# Carduino_v20.net
KiCad netlist of a schematic drawn in EAGLE
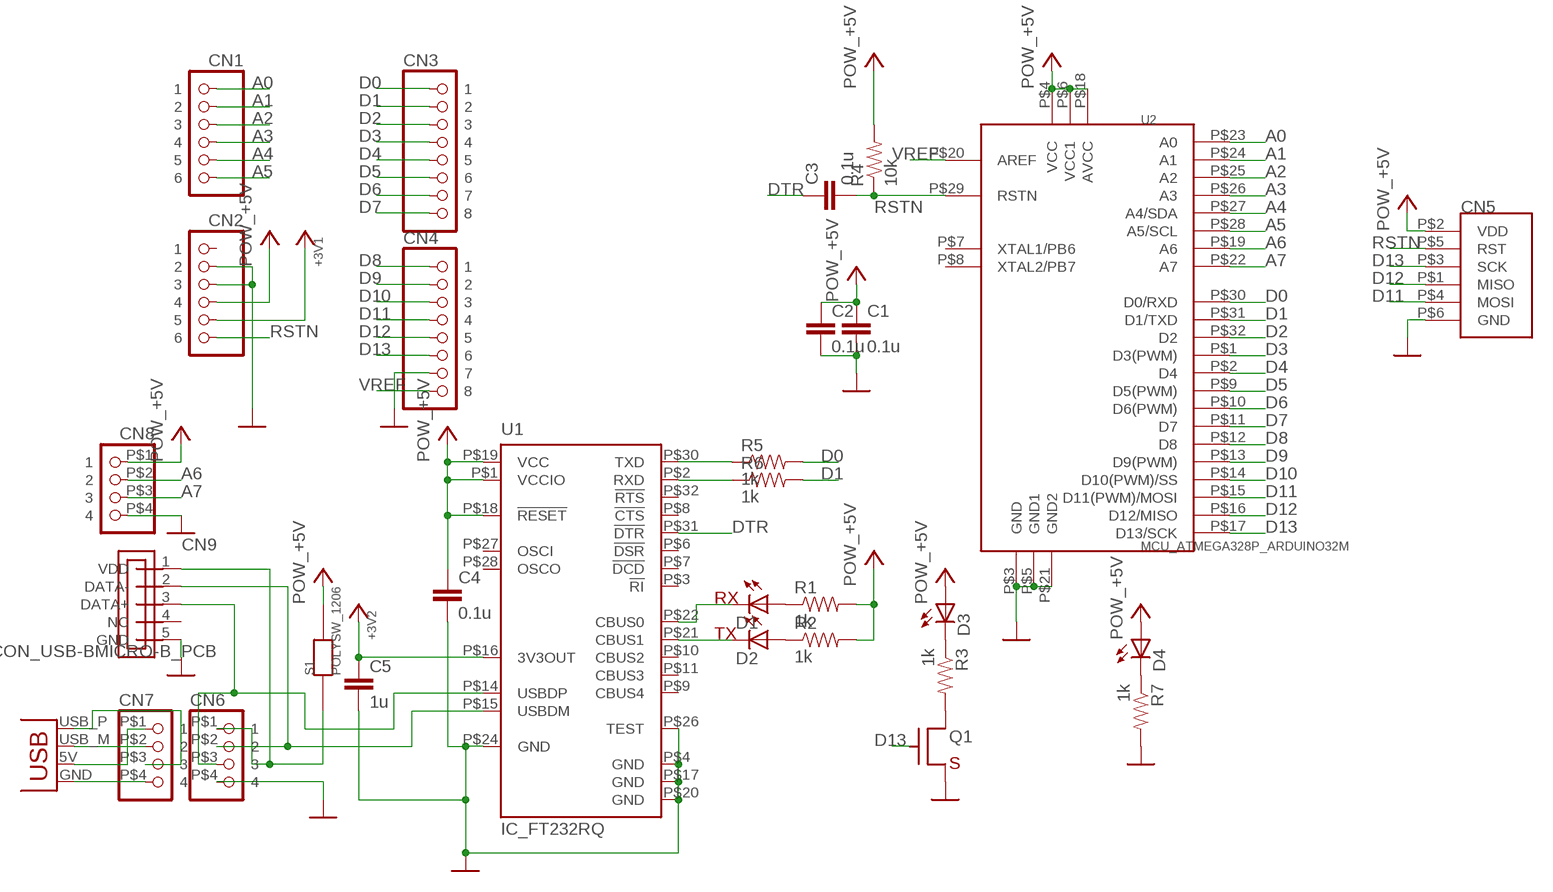
[diagram p0: schematic, sheet 1]

(export (version "E")
  (design (tool "Eeschema 10.0.6"))
  (components
    (comp (ref "C1")
      (value "0.1u")
      (footprint "eagle-import:0603")
      (libsource (lib "eagle-import") (part "CAP0603"))
    )
    (comp (ref "C2")
      (value "0.1u")
      (footprint "eagle-import:0603")
      (libsource (lib "eagle-import") (part "CAP0603"))
    )
    (comp (ref "C3")
      (value "0.1u")
      (footprint "eagle-import:0603")
      (libsource (lib "eagle-import") (part "CAP0603"))
    )
    (comp (ref "C4")
      (value "0.1u")
      (footprint "eagle-import:0603")
      (libsource (lib "eagle-import") (part "CAP0603"))
    )
    (comp (ref "C5")
      (value "1u")
      (footprint "eagle-import:0603")
      (libsource (lib "eagle-import") (part "CAP0603"))
    )
    (comp (ref "CN1")
      (value "CON_PINHD-1X6SMD")
      (footprint "eagle-import:1X06SMD")
      (libsource (lib "eagle-import") (part "CON_PINHD-1X6SMD"))
    )
    (comp (ref "CN2")
      (value "CON_PINHD-1X6SMD")
      (footprint "eagle-import:1X06SMD")
      (libsource (lib "eagle-import") (part "CON_PINHD-1X6SMD"))
    )
    (comp (ref "CN3")
      (value "CON_PINHD-1X8SMD")
      (footprint "eagle-import:1X08SMD")
      (libsource (lib "eagle-import") (part "CON_PINHD-1X8SMD"))
    )
    (comp (ref "CN4")
      (value "CON_PINHD-1X8SMD")
      (footprint "eagle-import:1X08SMD")
      (libsource (lib "eagle-import") (part "CON_PINHD-1X8SMD"))
    )
    (comp (ref "CN5")
      (value "CON_AVRISPSMD")
      (footprint "eagle-import:2X3SMD")
      (libsource (lib "eagle-import") (part "CON_AVRISPSMD"))
    )
    (comp (ref "CN6")
      (value "CON_PINHD-1X4SMD")
      (footprint "eagle-import:1X04SMD")
      (libsource (lib "eagle-import") (part "CON_PINHD-1X4SMD"))
    )
    (comp (ref "CN7")
      (value "CON_PINHD-1X4SMD")
      (footprint "eagle-import:1X04SMD")
      (libsource (lib "eagle-import") (part "CON_PINHD-1X4SMD"))
    )
    (comp (ref "CN8")
      (value "CON_PINHD-1X4SMD")
      (footprint "eagle-import:1X04SMD")
      (libsource (lib "eagle-import") (part "CON_PINHD-1X4SMD"))
    )
    (comp (ref "CN9")
      (value "CON_USB-BMICRO-B_PCB")
      (footprint "eagle-import:USB-MICRO-PCB")
      (libsource (lib "eagle-import") (part "CON_USB-BMICRO-B_PCB"))
    )
    (comp (ref "D1")
      (value "LED0603")
      (footprint "eagle-import:SPARKFUN_LED-0603")
      (libsource (lib "eagle-import") (part "LED0603"))
    )
    (comp (ref "D2")
      (value "LED0603")
      (footprint "eagle-import:SPARKFUN_LED-0603")
      (libsource (lib "eagle-import") (part "LED0603"))
    )
    (comp (ref "D3")
      (value "LED0603")
      (footprint "eagle-import:SPARKFUN_LED-0603")
      (libsource (lib "eagle-import") (part "LED0603"))
    )
    (comp (ref "D4")
      (value "LED0603")
      (footprint "eagle-import:SPARKFUN_LED-0603")
      (libsource (lib "eagle-import") (part "LED0603"))
    )
    (comp (ref "JP2")
      (value "CON_USBPCB")
      (footprint "eagle-import:USB-A-PCB")
      (libsource (lib "eagle-import") (part "CON_USBPCB"))
    )
    (comp (ref "Q1")
      (value "TR_NMOS_IRLML6344")
      (footprint "eagle-import:SOT-23-3-2916")
      (libsource (lib "eagle-import") (part "TR_NMOS_IRLML6344"))
    )
    (comp (ref "R1")
      (value "1k")
      (footprint "eagle-import:0603")
      (libsource (lib "eagle-import") (part "RES0603"))
    )
    (comp (ref "R2")
      (value "1k")
      (footprint "eagle-import:0603")
      (libsource (lib "eagle-import") (part "RES0603"))
    )
    (comp (ref "R3")
      (value "1k")
      (footprint "eagle-import:0603")
      (libsource (lib "eagle-import") (part "RES0603"))
    )
    (comp (ref "R4")
      (value "10k")
      (footprint "eagle-import:0603")
      (libsource (lib "eagle-import") (part "RES0603"))
    )
    (comp (ref "R5")
      (value "1k")
      (footprint "eagle-import:0603")
      (libsource (lib "eagle-import") (part "RES0603"))
    )
    (comp (ref "R6")
      (value "1k")
      (footprint "eagle-import:0603")
      (libsource (lib "eagle-import") (part "RES0603"))
    )
    (comp (ref "R7")
      (value "1k")
      (footprint "eagle-import:0603")
      (libsource (lib "eagle-import") (part "RES0603"))
    )
    (comp (ref "S1")
      (value "POLYSW_1206")
      (footprint "eagle-import:1206")
      (libsource (lib "eagle-import") (part "POLYSW_1206"))
    )
    (comp (ref "U1")
      (value "IC_FT232RQ")
      (footprint "eagle-import:QFN32")
      (libsource (lib "eagle-import") (part "IC_FT232RQ"))
    )
    (comp (ref "U2")
      (value "MCU_ATMEGA328P_ARDUINO32M")
      (footprint "eagle-import:QFN32")
      (libsource (lib "eagle-import") (part "MCU_ATMEGA328P_ARDUINO32M"))
    )
  )
  (nets
    (net (code "1") (name "/A0") (class "Default")
      (node (ref "CN1") (pin "P$1") (pinfunction "1_P$1") (pintype "passive"))
      (node (ref "U2") (pin "P$23") (pinfunction "A0_P$23") (pintype "bidirectional"))
    )
    (net (code "2") (name "/A1") (class "Default")
      (node (ref "CN1") (pin "P$2") (pinfunction "2_P$2") (pintype "passive"))
      (node (ref "U2") (pin "P$24") (pinfunction "A1_P$24") (pintype "bidirectional"))
    )
    (net (code "3") (name "/A2") (class "Default")
      (node (ref "CN1") (pin "P$3") (pinfunction "3_P$3") (pintype "passive"))
      (node (ref "U2") (pin "P$25") (pinfunction "A2_P$25") (pintype "bidirectional"))
    )
    (net (code "4") (name "/A3") (class "Default")
      (node (ref "CN1") (pin "P$4") (pinfunction "4_P$4") (pintype "passive"))
      (node (ref "U2") (pin "P$26") (pinfunction "A3_P$26") (pintype "bidirectional"))
    )
    (net (code "5") (name "/A4") (class "Default")
      (node (ref "CN1") (pin "P$5") (pinfunction "5_P$5") (pintype "passive"))
      (node (ref "U2") (pin "P$27") (pinfunction "A4/SDA_P$27") (pintype "bidirectional"))
    )
    (net (code "6") (name "/A5") (class "Default")
      (node (ref "CN1") (pin "P$6") (pinfunction "6_P$6") (pintype "passive"))
      (node (ref "U2") (pin "P$28") (pinfunction "A5/SCL_P$28") (pintype "bidirectional"))
    )
    (net (code "7") (name "/A6") (class "Default")
      (node (ref "CN8") (pin "P$2") (pinfunction "2_P$2") (pintype "passive"))
      (node (ref "U2") (pin "P$19") (pinfunction "A6_P$19") (pintype "bidirectional"))
    )
    (net (code "8") (name "/A7") (class "Default")
      (node (ref "CN8") (pin "P$3") (pinfunction "3_P$3") (pintype "passive"))
      (node (ref "U2") (pin "P$22") (pinfunction "A7_P$22") (pintype "bidirectional"))
    )
    (net (code "9") (name "/D0") (class "Default")
      (node (ref "CN3") (pin "P$1") (pinfunction "1_P$1") (pintype "passive"))
      (node (ref "R5") (pin "2") (pinfunction "2_2") (pintype "passive"))
      (node (ref "U2") (pin "P$30") (pinfunction "D0/RXD_P$30") (pintype "bidirectional"))
    )
    (net (code "10") (name "/D1") (class "Default")
      (node (ref "CN3") (pin "P$2") (pinfunction "2_P$2") (pintype "passive"))
      (node (ref "R6") (pin "2") (pinfunction "2_2") (pintype "passive"))
      (node (ref "U2") (pin "P$31") (pinfunction "D1/TXD_P$31") (pintype "bidirectional"))
    )
    (net (code "11") (name "/D2") (class "Default")
      (node (ref "CN3") (pin "P$3") (pinfunction "3_P$3") (pintype "passive"))
      (node (ref "U2") (pin "P$32") (pinfunction "D2_P$32") (pintype "bidirectional"))
    )
    (net (code "12") (name "/D3") (class "Default")
      (node (ref "CN3") (pin "P$4") (pinfunction "4_P$4") (pintype "passive"))
      (node (ref "U2") (pin "P$1") (pinfunction "D3(PWM)_P$1") (pintype "bidirectional"))
    )
    (net (code "13") (name "/D4") (class "Default")
      (node (ref "CN3") (pin "P$5") (pinfunction "5_P$5") (pintype "passive"))
      (node (ref "U2") (pin "P$2") (pinfunction "D4_P$2") (pintype "bidirectional"))
    )
    (net (code "14") (name "/D5") (class "Default")
      (node (ref "CN3") (pin "P$6") (pinfunction "6_P$6") (pintype "passive"))
      (node (ref "U2") (pin "P$9") (pinfunction "D5(PWM)_P$9") (pintype "bidirectional"))
    )
    (net (code "15") (name "/D6") (class "Default")
      (node (ref "CN3") (pin "P$7") (pinfunction "7_P$7") (pintype "passive"))
      (node (ref "U2") (pin "P$10") (pinfunction "D6(PWM)_P$10") (pintype "bidirectional"))
    )
    (net (code "16") (name "/D7") (class "Default")
      (node (ref "CN3") (pin "P$8") (pinfunction "8_P$8") (pintype "passive"))
      (node (ref "U2") (pin "P$11") (pinfunction "D7_P$11") (pintype "bidirectional"))
    )
    (net (code "17") (name "/D8") (class "Default")
      (node (ref "CN4") (pin "P$1") (pinfunction "1_P$1") (pintype "passive"))
      (node (ref "U2") (pin "P$12") (pinfunction "D8_P$12") (pintype "bidirectional"))
    )
    (net (code "18") (name "/D9") (class "Default")
      (node (ref "CN4") (pin "P$2") (pinfunction "2_P$2") (pintype "passive"))
      (node (ref "U2") (pin "P$13") (pinfunction "D9(PWM)_P$13") (pintype "bidirectional"))
    )
    (net (code "19") (name "/D10") (class "Default")
      (node (ref "CN4") (pin "P$3") (pinfunction "3_P$3") (pintype "passive"))
      (node (ref "U2") (pin "P$14") (pinfunction "D10(PWM)/SS_P$14") (pintype "bidirectional"))
    )
    (net (code "20") (name "/D11") (class "Default")
      (node (ref "CN4") (pin "P$4") (pinfunction "4_P$4") (pintype "passive"))
      (node (ref "CN5") (pin "P$4") (pinfunction "MOSI_P$4") (pintype "bidirectional"))
      (node (ref "U2") (pin "P$15") (pinfunction "D11(PWM)/MOSI_P$15") (pintype "bidirectional"))
    )
    (net (code "21") (name "/D12") (class "Default")
      (node (ref "CN4") (pin "P$5") (pinfunction "5_P$5") (pintype "passive"))
      (node (ref "CN5") (pin "P$1") (pinfunction "MISO_P$1") (pintype "bidirectional"))
      (node (ref "U2") (pin "P$16") (pinfunction "D12/MISO_P$16") (pintype "bidirectional"))
    )
    (net (code "22") (name "/D13") (class "Default")
      (node (ref "CN4") (pin "P$6") (pinfunction "6_P$6") (pintype "passive"))
      (node (ref "CN5") (pin "P$3") (pinfunction "SCK_P$3") (pintype "bidirectional"))
      (node (ref "Q1") (pin "1") (pinfunction "G_1") (pintype "bidirectional"))
      (node (ref "U2") (pin "P$17") (pinfunction "D13/SCK_P$17") (pintype "bidirectional"))
    )
    (net (code "23") (name "/DTR") (class "Default")
      (node (ref "C3") (pin "1") (pinfunction "1_1") (pintype "passive"))
      (node (ref "U1") (pin "P$31") (pinfunction "~{DTR}_P$31") (pintype "output"))
    )
    (net (code "24") (name "/RSTN") (class "Default")
      (node (ref "C3") (pin "2") (pinfunction "2_2") (pintype "passive"))
      (node (ref "CN2") (pin "P$6") (pinfunction "6_P$6") (pintype "passive"))
      (node (ref "CN5") (pin "P$5") (pinfunction "RST_P$5") (pintype "bidirectional"))
      (node (ref "R4") (pin "1") (pinfunction "1_1") (pintype "passive"))
      (node (ref "U2") (pin "P$29") (pinfunction "RSTN_P$29") (pintype "bidirectional"))
    )
    (net (code "25") (name "/VREF") (class "Default")
      (node (ref "CN4") (pin "P$8") (pinfunction "8_P$8") (pintype "passive"))
      (node (ref "U2") (pin "P$20") (pinfunction "AREF_P$20") (pintype "bidirectional"))
    )
    (net (code "26") (name "Net-(CN6-1)") (class "Default")
      (node (ref "CN6") (pin "P$1") (pinfunction "1_P$1") (pintype "passive"))
      (node (ref "CN9") (pin "1") (pinfunction "VDD_1") (pintype "power_in"))
      (node (ref "S1") (pin "P$1") (pinfunction "P$1_P$1") (pintype "bidirectional"))
    )
    (net (code "27") (name "Net-(CN6-2)") (class "Default")
      (node (ref "CN6") (pin "P$2") (pinfunction "2_P$2") (pintype "passive"))
      (node (ref "CN9") (pin "2") (pinfunction "DATA-_2") (pintype "bidirectional"))
      (node (ref "U1") (pin "P$15") (pinfunction "USBDM_P$15") (pintype "bidirectional"))
    )
    (net (code "28") (name "Net-(CN6-3)") (class "Default")
      (node (ref "CN6") (pin "P$3") (pinfunction "3_P$3") (pintype "passive"))
      (node (ref "CN9") (pin "3") (pinfunction "DATA+_3") (pintype "bidirectional"))
      (node (ref "U1") (pin "P$14") (pinfunction "USBDP_P$14") (pintype "bidirectional"))
    )
    (net (code "29") (name "Net-(CN7-1)") (class "Default")
      (node (ref "CN7") (pin "P$1") (pinfunction "1_P$1") (pintype "passive"))
      (node (ref "JP2") (pin "5V") (pinfunction "VBUS_5V") (pintype "bidirectional"))
    )
    (net (code "30") (name "Net-(CN7-2)") (class "Default")
      (node (ref "CN7") (pin "P$2") (pinfunction "2_P$2") (pintype "passive"))
      (node (ref "JP2") (pin "USB_M") (pinfunction "D-_USB_M") (pintype "bidirectional"))
    )
    (net (code "31") (name "Net-(CN7-3)") (class "Default")
      (node (ref "CN7") (pin "P$3") (pinfunction "3_P$3") (pintype "passive"))
      (node (ref "JP2") (pin "USB_P") (pinfunction "D+_USB_P") (pintype "bidirectional"))
    )
    (net (code "32") (name "Net-(CN7-4)") (class "Default")
      (node (ref "CN7") (pin "P$4") (pinfunction "4_P$4") (pintype "passive"))
      (node (ref "JP2") (pin "GND") (pinfunction "GND_GND") (pintype "bidirectional"))
    )
    (net (code "33") (name "Net-(D1-PadA)") (class "Default")
      (node (ref "D1") (pin "A") (pinfunction "A_A") (pintype "passive"))
      (node (ref "R1") (pin "1") (pinfunction "1_1") (pintype "passive"))
    )
    (net (code "34") (name "Net-(D2-PadA)") (class "Default")
      (node (ref "D2") (pin "A") (pinfunction "A_A") (pintype "passive"))
      (node (ref "R2") (pin "1") (pinfunction "1_1") (pintype "passive"))
    )
    (net (code "35") (name "Net-(D3-PadC)") (class "Default")
      (node (ref "D3") (pin "C") (pinfunction "C_C") (pintype "passive"))
      (node (ref "R3") (pin "1") (pinfunction "1_1") (pintype "passive"))
    )
    (net (code "36") (name "Net-(D4-PadC)") (class "Default")
      (node (ref "D4") (pin "C") (pinfunction "C_C") (pintype "passive"))
      (node (ref "R7") (pin "1") (pinfunction "1_1") (pintype "passive"))
    )
    (net (code "37") (name "Net-(Q1-D)") (class "Default")
      (node (ref "Q1") (pin "3") (pinfunction "D_3") (pintype "bidirectional"))
      (node (ref "R3") (pin "2") (pinfunction "2_2") (pintype "passive"))
    )
    (net (code "38") (name "Net-(U1-CBUS0)") (class "Default")
      (node (ref "D1") (pin "C") (pinfunction "C_C") (pintype "passive"))
      (node (ref "U1") (pin "P$22") (pinfunction "CBUS0_P$22") (pintype "bidirectional"))
    )
    (net (code "39") (name "Net-(U1-CBUS1)") (class "Default")
      (node (ref "D2") (pin "C") (pinfunction "C_C") (pintype "passive"))
      (node (ref "U1") (pin "P$21") (pinfunction "CBUS1_P$21") (pintype "bidirectional"))
    )
    (net (code "40") (name "Net-(U1-RXD)") (class "Default")
      (node (ref "R6") (pin "1") (pinfunction "1_1") (pintype "passive"))
      (node (ref "U1") (pin "P$2") (pinfunction "RXD_P$2") (pintype "input"))
    )
    (net (code "41") (name "Net-(U1-TXD)") (class "Default")
      (node (ref "R5") (pin "1") (pinfunction "1_1") (pintype "passive"))
      (node (ref "U1") (pin "P$30") (pinfunction "TXD_P$30") (pintype "output"))
    )
    (net (code "42") (name "POW_+3V3") (class "Default")
      (node (ref "C5") (pin "1") (pinfunction "1_1") (pintype "passive"))
      (node (ref "CN2") (pin "P$5") (pinfunction "5_P$5") (pintype "passive"))
      (node (ref "U1") (pin "P$16") (pinfunction "3V3OUT_P$16") (pintype "output"))
    )
    (net (code "43") (name "POW_+5V") (class "Default")
      (node (ref "C1") (pin "1") (pinfunction "1_1") (pintype "passive"))
      (node (ref "C2") (pin "1") (pinfunction "1_1") (pintype "passive"))
      (node (ref "C4") (pin "1") (pinfunction "1_1") (pintype "passive"))
      (node (ref "CN2") (pin "P$4") (pinfunction "4_P$4") (pintype "passive"))
      (node (ref "CN5") (pin "P$2") (pinfunction "VDD_P$2") (pintype "bidirectional"))
      (node (ref "CN8") (pin "P$1") (pinfunction "1_P$1") (pintype "passive"))
      (node (ref "D3") (pin "A") (pinfunction "A_A") (pintype "passive"))
      (node (ref "D4") (pin "A") (pinfunction "A_A") (pintype "passive"))
      (node (ref "R1") (pin "2") (pinfunction "2_2") (pintype "passive"))
      (node (ref "R2") (pin "2") (pinfunction "2_2") (pintype "passive"))
      (node (ref "R4") (pin "2") (pinfunction "2_2") (pintype "passive"))
      (node (ref "S1") (pin "P$2") (pinfunction "P$2_P$2") (pintype "bidirectional"))
      (node (ref "U1") (pin "P$1") (pinfunction "VCCIO_P$1") (pintype "power_in"))
      (node (ref "U1") (pin "P$18") (pinfunction "~{RESET}_P$18") (pintype "input"))
      (node (ref "U1") (pin "P$19") (pinfunction "VCC_P$19") (pintype "power_in"))
      (node (ref "U2") (pin "P$18") (pinfunction "AVCC_P$18") (pintype "power_in"))
      (node (ref "U2") (pin "P$4") (pinfunction "VCC_P$4") (pintype "power_in"))
      (node (ref "U2") (pin "P$6") (pinfunction "VCC1_P$6") (pintype "power_in"))
    )
    (net (code "44") (name "POW_GND") (class "Default")
      (node (ref "C1") (pin "2") (pinfunction "2_2") (pintype "passive"))
      (node (ref "C2") (pin "2") (pinfunction "2_2") (pintype "passive"))
      (node (ref "C4") (pin "2") (pinfunction "2_2") (pintype "passive"))
      (node (ref "C5") (pin "2") (pinfunction "2_2") (pintype "passive"))
      (node (ref "CN2") (pin "P$2") (pinfunction "2_P$2") (pintype "passive"))
      (node (ref "CN2") (pin "P$3") (pinfunction "3_P$3") (pintype "passive"))
      (node (ref "CN4") (pin "P$7") (pinfunction "7_P$7") (pintype "passive"))
      (node (ref "CN5") (pin "P$6") (pinfunction "GND_P$6") (pintype "bidirectional"))
      (node (ref "CN6") (pin "P$4") (pinfunction "4_P$4") (pintype "passive"))
      (node (ref "CN8") (pin "P$4") (pinfunction "4_P$4") (pintype "passive"))
      (node (ref "CN9") (pin "5") (pinfunction "GND_5") (pintype "power_in"))
      (node (ref "Q1") (pin "2") (pinfunction "S_2") (pintype "bidirectional"))
      (node (ref "R7") (pin "2") (pinfunction "2_2") (pintype "passive"))
      (node (ref "U1") (pin "P$17") (pinfunction "GND_P$17") (pintype "power_in"))
      (node (ref "U1") (pin "P$20") (pinfunction "GND_P$20") (pintype "power_in"))
      (node (ref "U1") (pin "P$24") (pinfunction "GND_P$24") (pintype "power_in"))
      (node (ref "U1") (pin "P$26") (pinfunction "TEST_P$26") (pintype "input"))
      (node (ref "U1") (pin "P$4") (pinfunction "GND_P$4") (pintype "power_in"))
      (node (ref "U2") (pin "P$21") (pinfunction "GND2_P$21") (pintype "power_in"))
      (node (ref "U2") (pin "P$3") (pinfunction "GND_P$3") (pintype "power_in"))
      (node (ref "U2") (pin "P$5") (pinfunction "GND1_P$5") (pintype "power_in"))
    )
    (net (code "45") (name "unconnected-(CN2-1-PadP$1)") (class "Default")
      (node (ref "CN2") (pin "P$1") (pinfunction "1_P$1") (pintype "passive"))
    )
    (net (code "46") (name "unconnected-(CN9-NC-Pad4)") (class "Default")
      (node (ref "CN9") (pin "4") (pinfunction "NC_4") (pintype "bidirectional"))
    )
    (net (code "47") (name "unconnected-(U1-CBUS2-PadP$10)") (class "Default")
      (node (ref "U1") (pin "P$10") (pinfunction "CBUS2_P$10") (pintype "bidirectional"))
    )
    (net (code "48") (name "unconnected-(U1-CBUS3-PadP$11)") (class "Default")
      (node (ref "U1") (pin "P$11") (pinfunction "CBUS3_P$11") (pintype "bidirectional"))
    )
    (net (code "49") (name "unconnected-(U1-CBUS4-PadP$9)") (class "Default")
      (node (ref "U1") (pin "P$9") (pinfunction "CBUS4_P$9") (pintype "bidirectional"))
    )
    (net (code "50") (name "unconnected-(U1-OSCI-PadP$27)") (class "Default")
      (node (ref "U1") (pin "P$27") (pinfunction "OSCI_P$27") (pintype "input"))
    )
    (net (code "51") (name "unconnected-(U1-OSCO-PadP$28)") (class "Default")
      (node (ref "U1") (pin "P$28") (pinfunction "OSCO_P$28") (pintype "output"))
    )
    (net (code "52") (name "unconnected-(U1-~{CTS}-PadP$8)") (class "Default")
      (node (ref "U1") (pin "P$8") (pinfunction "~{CTS}_P$8") (pintype "input"))
    )
    (net (code "53") (name "unconnected-(U1-~{DCD}-PadP$7)") (class "Default")
      (node (ref "U1") (pin "P$7") (pinfunction "~{DCD}_P$7") (pintype "input"))
    )
    (net (code "54") (name "unconnected-(U1-~{DSR}-PadP$6)") (class "Default")
      (node (ref "U1") (pin "P$6") (pinfunction "~{DSR}_P$6") (pintype "input"))
    )
    (net (code "55") (name "unconnected-(U1-~{RI}-PadP$3)") (class "Default")
      (node (ref "U1") (pin "P$3") (pinfunction "~{RI}_P$3") (pintype "input"))
    )
    (net (code "56") (name "unconnected-(U1-~{RTS}-PadP$32)") (class "Default")
      (node (ref "U1") (pin "P$32") (pinfunction "~{RTS}_P$32") (pintype "output"))
    )
    (net (code "57") (name "unconnected-(U2-XTAL1{slash}PB6-PadP$7)") (class "Default")
      (node (ref "U2") (pin "P$7") (pinfunction "XTAL1/PB6_P$7") (pintype "bidirectional"))
    )
    (net (code "58") (name "unconnected-(U2-XTAL2{slash}PB7-PadP$8)") (class "Default")
      (node (ref "U2") (pin "P$8") (pinfunction "XTAL2/PB7_P$8") (pintype "bidirectional"))
    )
  )
)
